# BatBoostAAA.net
KiCad netlist of a schematic drawn in EAGLE
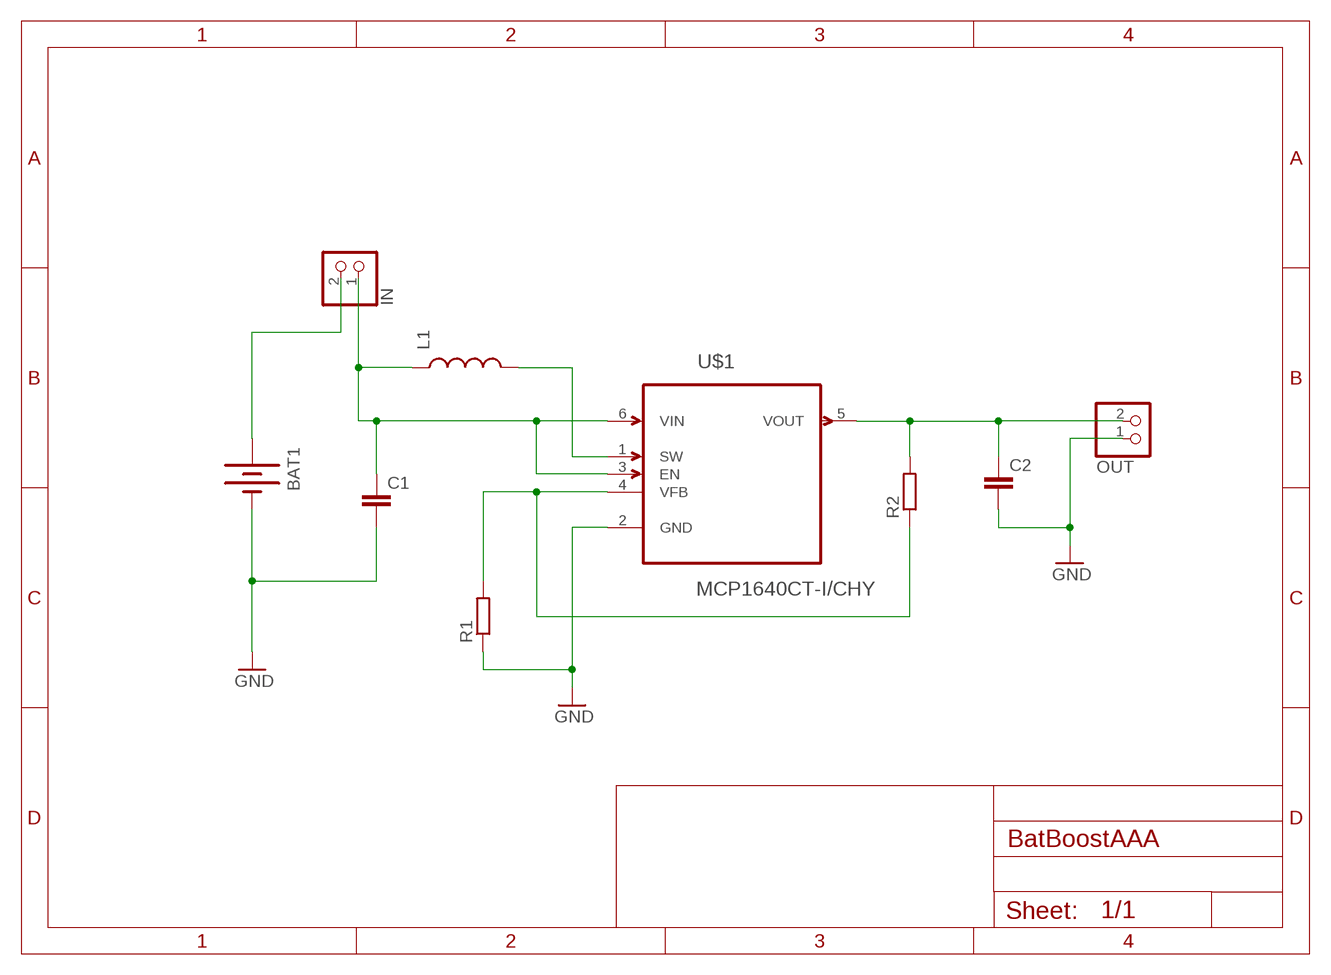
[diagram p0: schematic, sheet 1]

(export (version "E")
  (design (tool "Eeschema 10.0.6"))
  (components
    (comp (ref "BAT1")
      (value "BATTERYAAA")
      (footprint "eagle-import:BATTERY-AAA")
      (libsource (lib "eagle-import") (part "BATTERYAAA"))
    )
    (comp (ref "C1")
      (value "C-EUC0805K")
      (footprint "eagle-import:C0805K")
      (libsource (lib "eagle-import") (part "C-EUC0805K"))
    )
    (comp (ref "C2")
      (value "C-EUC0805K")
      (footprint "eagle-import:C0805K")
      (libsource (lib "eagle-import") (part "C-EUC0805K"))
    )
    (comp (ref "IN")
      (value "PINHD-1X2")
      (footprint "eagle-import:1X02")
      (libsource (lib "eagle-import") (part "PINHD-1X2"))
    )
    (comp (ref "L1")
      (value "INDUCTOR1210")
      (footprint "eagle-import:LQH32")
      (libsource (lib "eagle-import") (part "INDUCTOR1210"))
    )
    (comp (ref "OUT")
      (value "PINHD-1X2")
      (footprint "eagle-import:1X02")
      (libsource (lib "eagle-import") (part "PINHD-1X2"))
    )
    (comp (ref "R1")
      (value "R-EU_R0603")
      (footprint "eagle-import:R0603")
      (libsource (lib "eagle-import") (part "R-EU_R0603"))
    )
    (comp (ref "R2")
      (value "R-EU_R0603")
      (footprint "eagle-import:R0603")
      (libsource (lib "eagle-import") (part "R-EU_R0603"))
    )
    (comp (ref "U$1")
      (value "MCP1640CT-I/CHY")
      (footprint "eagle-import:SOT95P270X145-6N")
      (libsource (lib "eagle-import") (part "MCP1640CT-I/CHY"))
    )
  )
  (nets
    (net (code "1") (name "GND") (class "Default")
      (node (ref "BAT1") (pin "GND@1") (pinfunction "-_GND@1") (pintype "power_in"))
      (node (ref "C1") (pin "2") (pinfunction "2_2") (pintype "passive"))
      (node (ref "C2") (pin "2") (pinfunction "2_2") (pintype "passive"))
      (node (ref "OUT") (pin "1") (pinfunction "1_1") (pintype "passive"))
      (node (ref "R1") (pin "1") (pinfunction "1_1") (pintype "passive"))
      (node (ref "U$1") (pin "2") (pinfunction "GND_2") (pintype "passive"))
    )
    (net (code "2") (name "Net-(BAT1-+)") (class "Default")
      (node (ref "BAT1") (pin "PWR@1") (pinfunction "+_PWR@1") (pintype "power_in"))
      (node (ref "IN") (pin "2") (pinfunction "2_2") (pintype "passive"))
    )
    (net (code "3") (name "Net-(U$1-EN)") (class "Default")
      (node (ref "C1") (pin "1") (pinfunction "1_1") (pintype "passive"))
      (node (ref "IN") (pin "1") (pinfunction "1_1") (pintype "passive"))
      (node (ref "L1") (pin "1") (pinfunction "1_1") (pintype "passive"))
      (node (ref "U$1") (pin "3") (pinfunction "EN_3") (pintype "input"))
      (node (ref "U$1") (pin "6") (pinfunction "VIN_6") (pintype "input"))
    )
    (net (code "4") (name "Net-(U$1-SW)") (class "Default")
      (node (ref "L1") (pin "2") (pinfunction "2_2") (pintype "passive"))
      (node (ref "U$1") (pin "1") (pinfunction "SW_1") (pintype "input"))
    )
    (net (code "5") (name "Net-(U$1-VFB)") (class "Default")
      (node (ref "R1") (pin "2") (pinfunction "2_2") (pintype "passive"))
      (node (ref "R2") (pin "1") (pinfunction "1_1") (pintype "passive"))
      (node (ref "U$1") (pin "4") (pinfunction "VFB_4") (pintype "input"))
    )
    (net (code "6") (name "Net-(U$1-VOUT)") (class "Default")
      (node (ref "C2") (pin "1") (pinfunction "1_1") (pintype "passive"))
      (node (ref "OUT") (pin "2") (pinfunction "2_2") (pintype "passive"))
      (node (ref "R2") (pin "2") (pinfunction "2_2") (pintype "passive"))
      (node (ref "U$1") (pin "5") (pinfunction "VOUT_5") (pintype "output"))
    )
  )
)
